# SD_Card.net
KiCad netlist of a schematic drawn in Altium Designer
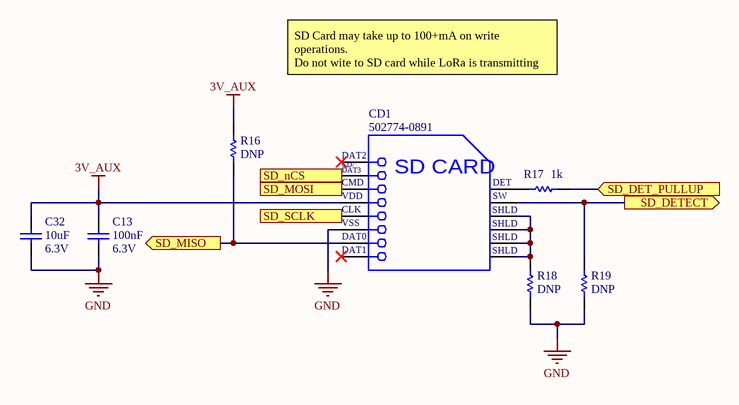
[diagram p0: SD Card.SchDoc]

(export (version "E")
  (design (tool "Eeschema 10.0.6"))
  (components
    (comp (ref "C13")
      (value "100nF")
      (footprint "0603 (1608M)")
      (description "Capacitor")
      (fields (field (name "VOLTAGE") "6.3V") (field (name "Comment") "Cap"))
      (libsource (lib "components") (part "Cap"))
    )
    (comp (ref "C32")
      (value "10uF")
      (footprint "0603 (1608M)")
      (description "Capacitor")
      (fields (field (name "VOLTAGE") "6.3V") (field (name "Comment") "Cap"))
      (libsource (lib "components") (part "Cap"))
    )
    (comp (ref "CD1")
      (value "502774-0891")
      (footprint "MOLX-502774-0891_V")
      (description "Micro SD Memory Card Connector, 0.5 A, 10 V (DC), -25 to 85 degC, 8-Pin SMT, RoHS, Tape and Reel")
      (fields (field (name "MANUFACTURER") "Molex"))
      (libsource (lib "Altium Content Vault") (part "CN-SD-8-2SW-4S_B"))
    )
    (comp (ref "R16")
      (value "DNP")
      (footprint "0603 (1608M)")
      (description "Resistor")
      (fields (field (name "TOLERANCE") "5%") (field (name "PUBLISHER") "Altium Limited"))
      (libsource (lib "components") (part "Resistor"))
    )
    (comp (ref "R17")
      (value "1k")
      (footprint "0603 (1608M)")
      (description "Resistor")
      (fields (field (name "TOLERANCE") "5%") (field (name "PUBLISHER") "Altium Limited"))
      (libsource (lib "components") (part "Resistor"))
    )
    (comp (ref "R18")
      (value "DNP")
      (footprint "0603 (1608M)")
      (description "Resistor")
      (fields (field (name "TOLERANCE") "5%") (field (name "PUBLISHER") "Altium Limited"))
      (libsource (lib "components") (part "Resistor"))
    )
    (comp (ref "R19")
      (value "DNP")
      (footprint "0603 (1608M)")
      (description "Resistor")
      (fields (field (name "TOLERANCE") "5%") (field (name "PUBLISHER") "Altium Limited"))
      (libsource (lib "components") (part "Resistor"))
    )
  )
  (nets
    (net (code "1") (name "/SD_DETECT") (class "Default")
      (node (ref "CD1") (pin "10") (pinfunction "SWITCH_10") (pintype "passive"))
      (node (ref "R19") (pin "2") (pinfunction "2_2") (pintype "passive"))
    )
    (net (code "2") (name "/SD_DET_PULLUP") (class "Default")
      (node (ref "R17") (pin "1") (pinfunction "1_1") (pintype "passive"))
    )
    (net (code "3") (name "/SD_MISO") (class "Default")
      (node (ref "CD1") (pin "7") (pinfunction "DAT0_7") (pintype "passive"))
      (node (ref "R16") (pin "1") (pinfunction "1_1") (pintype "passive"))
    )
    (net (code "4") (name "/SD_MOSI") (class "Default")
      (node (ref "CD1") (pin "3") (pinfunction "CMD_3") (pintype "passive"))
    )
    (net (code "5") (name "/SD_SCLK") (class "Default")
      (node (ref "CD1") (pin "5") (pinfunction "CLK_5") (pintype "passive"))
    )
    (net (code "6") (name "/SD_nCS") (class "Default")
      (node (ref "CD1") (pin "2") (pinfunction "CD/DAT3_2") (pintype "passive"))
    )
    (net (code "7") (name "3V_AUX") (class "Default")
      (node (ref "C13") (pin "2") (pinfunction "2_2") (pintype "passive"))
      (node (ref "C32") (pin "2") (pinfunction "2_2") (pintype "passive"))
      (node (ref "CD1") (pin "4") (pinfunction "VDD_4") (pintype "passive"))
      (node (ref "R16") (pin "2") (pinfunction "2_2") (pintype "passive"))
    )
    (net (code "8") (name "GND") (class "Default")
      (node (ref "C13") (pin "1") (pinfunction "1_1") (pintype "passive"))
      (node (ref "C32") (pin "1") (pinfunction "1_1") (pintype "passive"))
      (node (ref "CD1") (pin "6") (pinfunction "VSS_6") (pintype "passive"))
      (node (ref "R18") (pin "1") (pinfunction "1_1") (pintype "passive"))
      (node (ref "R19") (pin "1") (pinfunction "1_1") (pintype "passive"))
    )
    (net (code "9") (name "Net-(CD1-DETECT)") (class "Default")
      (node (ref "CD1") (pin "9") (pinfunction "DETECT_9") (pintype "passive"))
      (node (ref "R17") (pin "2") (pinfunction "2_2") (pintype "passive"))
    )
    (net (code "10") (name "Net-(CD1-SHLD-Pad11)") (class "Default")
      (node (ref "CD1") (pin "11") (pinfunction "SHLD_11") (pintype "passive"))
      (node (ref "CD1") (pin "12") (pinfunction "SHLD_12") (pintype "passive"))
      (node (ref "CD1") (pin "13") (pinfunction "SHLD_13") (pintype "passive"))
      (node (ref "CD1") (pin "14") (pinfunction "SHLD_14") (pintype "passive"))
      (node (ref "R18") (pin "2") (pinfunction "2_2") (pintype "passive"))
    )
    (net (code "11") (name "unconnected-(CD1-DAT1-Pad8)") (class "Default")
      (node (ref "CD1") (pin "8") (pinfunction "DAT1_8") (pintype "passive+no_connect"))
    )
    (net (code "12") (name "unconnected-(CD1-DAT2-Pad1)") (class "Default")
      (node (ref "CD1") (pin "1") (pinfunction "DAT2_1") (pintype "passive+no_connect"))
    )
  )
)
